# OperantFEDv6.net
KiCad netlist of a schematic drawn in EAGLE
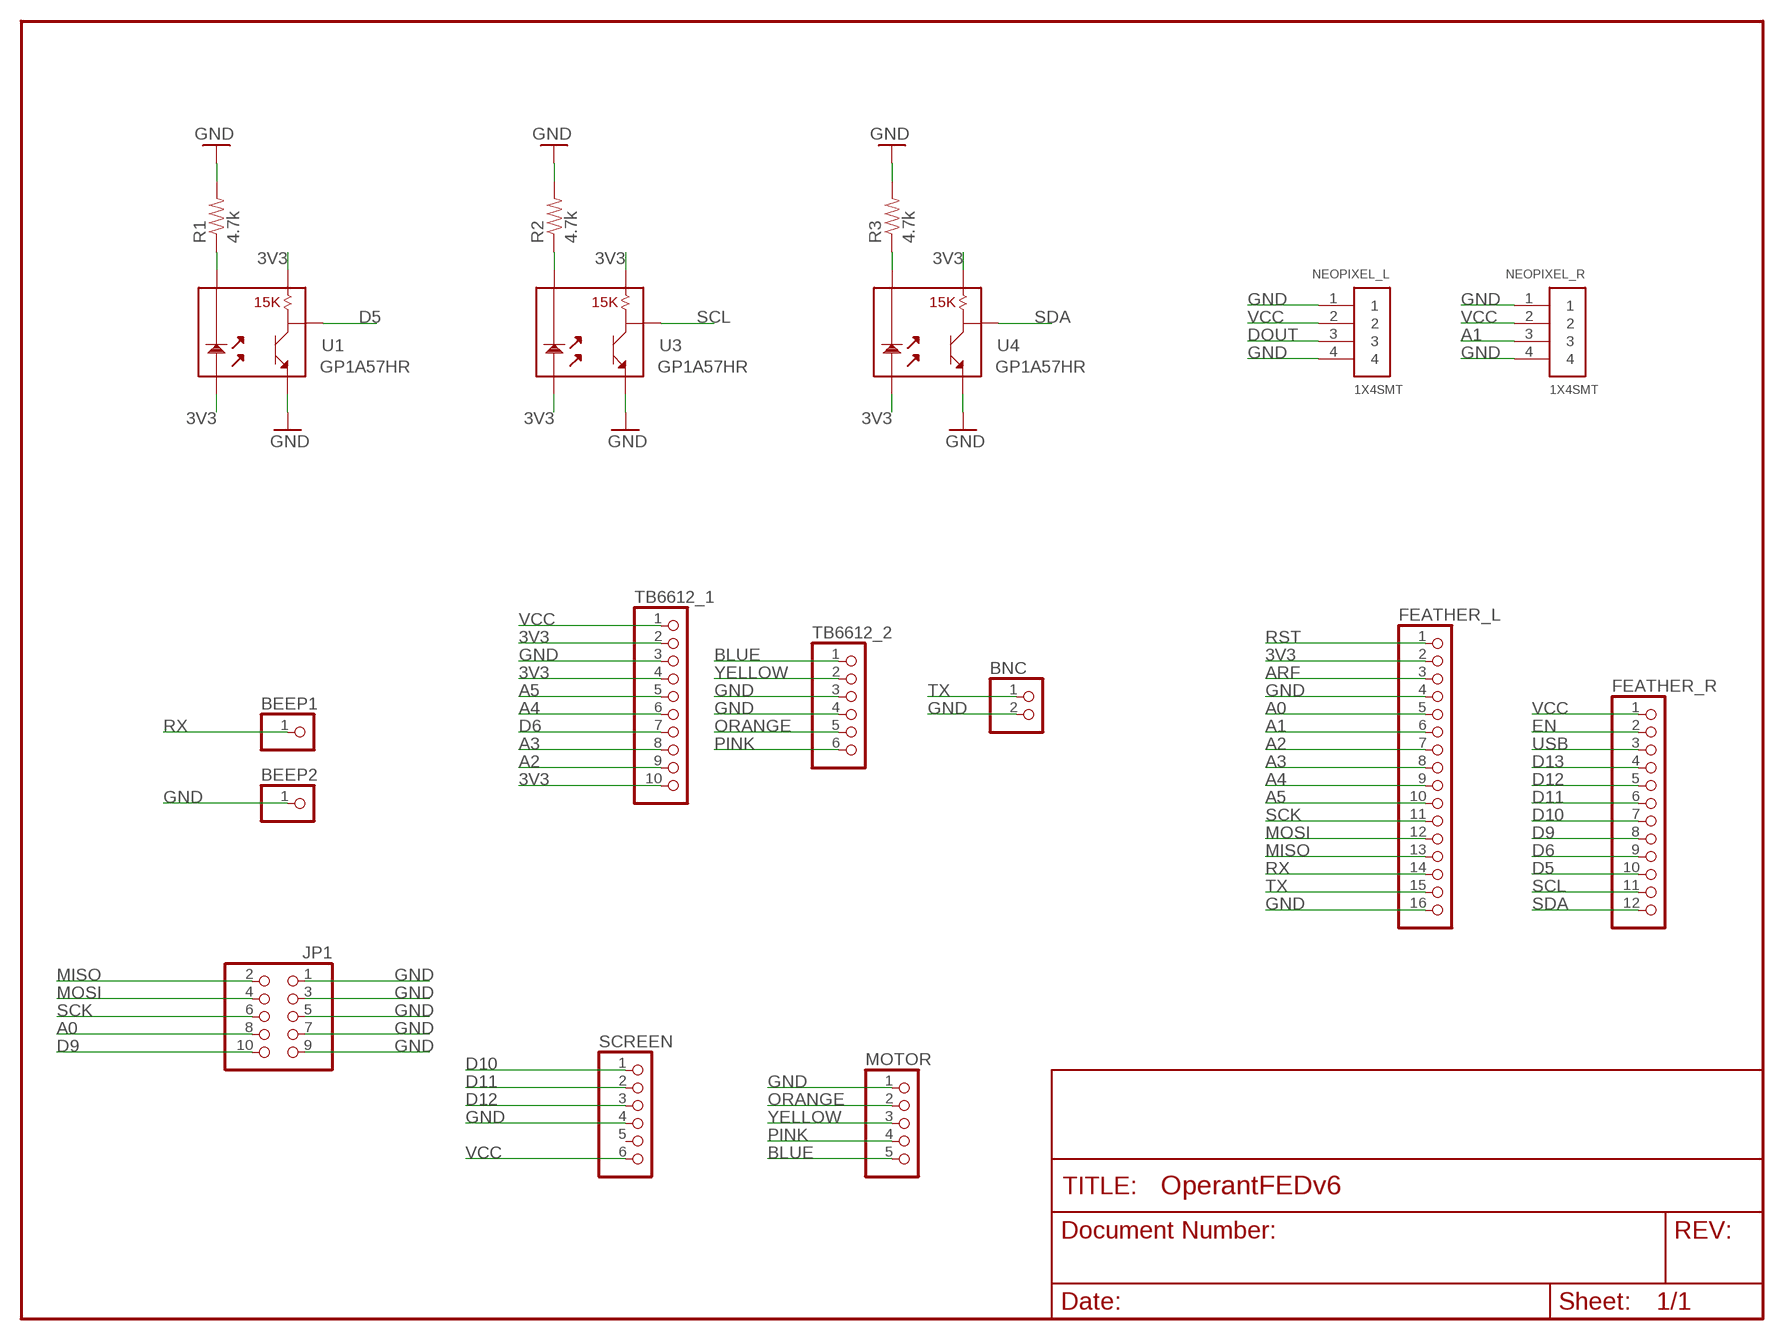
[diagram p0: schematic, sheet 1]

(export (version "E")
  (design (tool "Eeschema 10.0.6"))
  (components
    (comp (ref "BEEP1")
      (value "PINHD-1X1")
      (footprint "eagle-import:1X01")
      (libsource (lib "eagle-import") (part "PINHD-1X1"))
    )
    (comp (ref "BEEP2")
      (value "PINHD-1X1")
      (footprint "eagle-import:1X01")
      (libsource (lib "eagle-import") (part "PINHD-1X1"))
    )
    (comp (ref "BNC")
      (value "PINHD-1X2")
      (footprint "eagle-import:1X02")
      (libsource (lib "eagle-import") (part "PINHD-1X2"))
    )
    (comp (ref "FEATHER_L")
      (value "PINHD-1X16")
      (footprint "eagle-import:1X16")
      (libsource (lib "eagle-import") (part "PINHD-1X16"))
    )
    (comp (ref "FEATHER_R")
      (value "PINHD-1X12")
      (footprint "eagle-import:1X12")
      (libsource (lib "eagle-import") (part "PINHD-1X12"))
    )
    (comp (ref "JP1")
      (value "PINHD-2X5/90")
      (footprint "eagle-import:2X05_90")
      (libsource (lib "eagle-import") (part "PINHD-2X5/90"))
    )
    (comp (ref "MOTOR")
      (value "PINHD-1X5")
      (footprint "eagle-import:1X05")
      (libsource (lib "eagle-import") (part "PINHD-1X5"))
    )
    (comp (ref "NEOPIXEL_L")
      (value "1X4SMT")
      (footprint "eagle-import:1X4-SMT")
      (libsource (lib "eagle-import") (part "1X4SMT"))
    )
    (comp (ref "NEOPIXEL_R")
      (value "1X4SMT")
      (footprint "eagle-import:1X4-SMT")
      (libsource (lib "eagle-import") (part "1X4SMT"))
    )
    (comp (ref "R1")
      (value "4.7k")
      (footprint "eagle-import:AXIAL-0.3")
      (libsource (lib "eagle-import") (part "RESISTORPTH1"))
    )
    (comp (ref "R2")
      (value "4.7k")
      (footprint "eagle-import:AXIAL-0.3")
      (libsource (lib "eagle-import") (part "RESISTORPTH1"))
    )
    (comp (ref "R3")
      (value "4.7k")
      (footprint "eagle-import:AXIAL-0.3")
      (libsource (lib "eagle-import") (part "RESISTORPTH1"))
    )
    (comp (ref "SCREEN")
      (value "PINHD-1X6")
      (footprint "eagle-import:1X06")
      (libsource (lib "eagle-import") (part "PINHD-1X6"))
    )
    (comp (ref "TB6612_1")
      (value "PINHD-1X10")
      (footprint "eagle-import:1X10")
      (libsource (lib "eagle-import") (part "PINHD-1X10"))
    )
    (comp (ref "TB6612_2")
      (value "PINHD-1X6")
      (footprint "eagle-import:1X06")
      (libsource (lib "eagle-import") (part "PINHD-1X6"))
    )
    (comp (ref "U1")
      (value "GP1A57HR")
      (footprint "eagle-import:GP1A57HR")
      (libsource (lib "eagle-import") (part "GP1A57HR"))
    )
    (comp (ref "U3")
      (value "GP1A57HR")
      (footprint "eagle-import:GP1A57HR")
      (libsource (lib "eagle-import") (part "GP1A57HR"))
    )
    (comp (ref "U4")
      (value "GP1A57HR")
      (footprint "eagle-import:GP1A57HR")
      (libsource (lib "eagle-import") (part "GP1A57HR"))
    )
  )
  (nets
    (net (code "1") (name "/3V3") (class "Default")
      (node (ref "FEATHER_L") (pin "2") (pinfunction "2_2") (pintype "passive"))
      (node (ref "TB6612_1") (pin "10") (pinfunction "10_10") (pintype "passive"))
      (node (ref "TB6612_1") (pin "2") (pinfunction "2_2") (pintype "passive"))
      (node (ref "TB6612_1") (pin "4") (pinfunction "4_4") (pintype "passive"))
      (node (ref "U1") (pin "1") (pinfunction "1_1") (pintype "bidirectional"))
      (node (ref "U1") (pin "3") (pinfunction "3_3") (pintype "bidirectional"))
      (node (ref "U3") (pin "1") (pinfunction "1_1") (pintype "bidirectional"))
      (node (ref "U3") (pin "3") (pinfunction "3_3") (pintype "bidirectional"))
      (node (ref "U4") (pin "1") (pinfunction "1_1") (pintype "bidirectional"))
      (node (ref "U4") (pin "3") (pinfunction "3_3") (pintype "bidirectional"))
    )
    (net (code "2") (name "/A0") (class "Default")
      (node (ref "FEATHER_L") (pin "5") (pinfunction "5_5") (pintype "passive"))
      (node (ref "JP1") (pin "8") (pinfunction "8_8") (pintype "passive"))
    )
    (net (code "3") (name "/A1") (class "Default")
      (node (ref "FEATHER_L") (pin "6") (pinfunction "6_6") (pintype "passive"))
      (node (ref "NEOPIXEL_R") (pin "3") (pinfunction "3_3") (pintype "bidirectional"))
    )
    (net (code "4") (name "/A2") (class "Default")
      (node (ref "FEATHER_L") (pin "7") (pinfunction "7_7") (pintype "passive"))
      (node (ref "TB6612_1") (pin "9") (pinfunction "9_9") (pintype "passive"))
    )
    (net (code "5") (name "/A3") (class "Default")
      (node (ref "FEATHER_L") (pin "8") (pinfunction "8_8") (pintype "passive"))
      (node (ref "TB6612_1") (pin "8") (pinfunction "8_8") (pintype "passive"))
    )
    (net (code "6") (name "/A4") (class "Default")
      (node (ref "FEATHER_L") (pin "9") (pinfunction "9_9") (pintype "passive"))
      (node (ref "TB6612_1") (pin "6") (pinfunction "6_6") (pintype "passive"))
    )
    (net (code "7") (name "/A5") (class "Default")
      (node (ref "FEATHER_L") (pin "10") (pinfunction "10_10") (pintype "passive"))
      (node (ref "TB6612_1") (pin "5") (pinfunction "5_5") (pintype "passive"))
    )
    (net (code "8") (name "/ARF") (class "Default")
      (node (ref "FEATHER_L") (pin "3") (pinfunction "3_3") (pintype "passive"))
    )
    (net (code "9") (name "/BLUE") (class "Default")
      (node (ref "MOTOR") (pin "5") (pinfunction "5_5") (pintype "passive"))
      (node (ref "TB6612_2") (pin "1") (pinfunction "1_1") (pintype "passive"))
    )
    (net (code "10") (name "/D5") (class "Default")
      (node (ref "FEATHER_R") (pin "10") (pinfunction "10_10") (pintype "passive"))
      (node (ref "U1") (pin "4") (pinfunction "4_4") (pintype "bidirectional"))
    )
    (net (code "11") (name "/D6") (class "Default")
      (node (ref "FEATHER_R") (pin "9") (pinfunction "9_9") (pintype "passive"))
      (node (ref "TB6612_1") (pin "7") (pinfunction "7_7") (pintype "passive"))
    )
    (net (code "12") (name "/D9") (class "Default")
      (node (ref "FEATHER_R") (pin "8") (pinfunction "8_8") (pintype "passive"))
      (node (ref "JP1") (pin "10") (pinfunction "10_10") (pintype "passive"))
    )
    (net (code "13") (name "/D10") (class "Default")
      (node (ref "FEATHER_R") (pin "7") (pinfunction "7_7") (pintype "passive"))
      (node (ref "SCREEN") (pin "1") (pinfunction "1_1") (pintype "passive"))
    )
    (net (code "14") (name "/D11") (class "Default")
      (node (ref "FEATHER_R") (pin "6") (pinfunction "6_6") (pintype "passive"))
      (node (ref "SCREEN") (pin "2") (pinfunction "2_2") (pintype "passive"))
    )
    (net (code "15") (name "/D12") (class "Default")
      (node (ref "FEATHER_R") (pin "5") (pinfunction "5_5") (pintype "passive"))
      (node (ref "SCREEN") (pin "3") (pinfunction "3_3") (pintype "passive"))
    )
    (net (code "16") (name "/D13") (class "Default")
      (node (ref "FEATHER_R") (pin "4") (pinfunction "4_4") (pintype "passive"))
    )
    (net (code "17") (name "/DOUT") (class "Default")
      (node (ref "NEOPIXEL_L") (pin "3") (pinfunction "3_3") (pintype "bidirectional"))
    )
    (net (code "18") (name "/EN") (class "Default")
      (node (ref "FEATHER_R") (pin "2") (pinfunction "2_2") (pintype "passive"))
    )
    (net (code "19") (name "/MISO") (class "Default")
      (node (ref "FEATHER_L") (pin "13") (pinfunction "13_13") (pintype "passive"))
      (node (ref "JP1") (pin "2") (pinfunction "2_2") (pintype "passive"))
    )
    (net (code "20") (name "/MOSI") (class "Default")
      (node (ref "FEATHER_L") (pin "12") (pinfunction "12_12") (pintype "passive"))
      (node (ref "JP1") (pin "4") (pinfunction "4_4") (pintype "passive"))
    )
    (net (code "21") (name "/ORANGE") (class "Default")
      (node (ref "MOTOR") (pin "2") (pinfunction "2_2") (pintype "passive"))
      (node (ref "TB6612_2") (pin "5") (pinfunction "5_5") (pintype "passive"))
    )
    (net (code "22") (name "/PINK") (class "Default")
      (node (ref "MOTOR") (pin "4") (pinfunction "4_4") (pintype "passive"))
      (node (ref "TB6612_2") (pin "6") (pinfunction "6_6") (pintype "passive"))
    )
    (net (code "23") (name "/RST") (class "Default")
      (node (ref "FEATHER_L") (pin "1") (pinfunction "1_1") (pintype "passive"))
    )
    (net (code "24") (name "/RX") (class "Default")
      (node (ref "BEEP1") (pin "1") (pinfunction "1_1") (pintype "passive"))
      (node (ref "FEATHER_L") (pin "14") (pinfunction "14_14") (pintype "passive"))
    )
    (net (code "25") (name "/SCK") (class "Default")
      (node (ref "FEATHER_L") (pin "11") (pinfunction "11_11") (pintype "passive"))
      (node (ref "JP1") (pin "6") (pinfunction "6_6") (pintype "passive"))
    )
    (net (code "26") (name "/SCL") (class "Default")
      (node (ref "FEATHER_R") (pin "11") (pinfunction "11_11") (pintype "passive"))
      (node (ref "U3") (pin "4") (pinfunction "4_4") (pintype "bidirectional"))
    )
    (net (code "27") (name "/SDA") (class "Default")
      (node (ref "FEATHER_R") (pin "12") (pinfunction "12_12") (pintype "passive"))
      (node (ref "U4") (pin "4") (pinfunction "4_4") (pintype "bidirectional"))
    )
    (net (code "28") (name "/TX") (class "Default")
      (node (ref "BNC") (pin "1") (pinfunction "1_1") (pintype "passive"))
      (node (ref "FEATHER_L") (pin "15") (pinfunction "15_15") (pintype "passive"))
    )
    (net (code "29") (name "/USB") (class "Default")
      (node (ref "FEATHER_R") (pin "3") (pinfunction "3_3") (pintype "passive"))
    )
    (net (code "30") (name "/VCC") (class "Default")
      (node (ref "FEATHER_R") (pin "1") (pinfunction "1_1") (pintype "passive"))
      (node (ref "NEOPIXEL_L") (pin "2") (pinfunction "2_2") (pintype "bidirectional"))
      (node (ref "NEOPIXEL_R") (pin "2") (pinfunction "2_2") (pintype "bidirectional"))
      (node (ref "SCREEN") (pin "6") (pinfunction "6_6") (pintype "passive"))
      (node (ref "TB6612_1") (pin "1") (pinfunction "1_1") (pintype "passive"))
    )
    (net (code "31") (name "/YELLOW") (class "Default")
      (node (ref "MOTOR") (pin "3") (pinfunction "3_3") (pintype "passive"))
      (node (ref "TB6612_2") (pin "2") (pinfunction "2_2") (pintype "passive"))
    )
    (net (code "32") (name "GND") (class "Default")
      (node (ref "BEEP2") (pin "1") (pinfunction "1_1") (pintype "passive"))
      (node (ref "BNC") (pin "2") (pinfunction "2_2") (pintype "passive"))
      (node (ref "FEATHER_L") (pin "16") (pinfunction "16_16") (pintype "passive"))
      (node (ref "FEATHER_L") (pin "4") (pinfunction "4_4") (pintype "passive"))
      (node (ref "JP1") (pin "1") (pinfunction "1_1") (pintype "passive"))
      (node (ref "JP1") (pin "3") (pinfunction "3_3") (pintype "passive"))
      (node (ref "JP1") (pin "5") (pinfunction "5_5") (pintype "passive"))
      (node (ref "JP1") (pin "7") (pinfunction "7_7") (pintype "passive"))
      (node (ref "JP1") (pin "9") (pinfunction "9_9") (pintype "passive"))
      (node (ref "MOTOR") (pin "1") (pinfunction "1_1") (pintype "passive"))
      (node (ref "NEOPIXEL_L") (pin "1") (pinfunction "1_1") (pintype "bidirectional"))
      (node (ref "NEOPIXEL_L") (pin "4") (pinfunction "4_4") (pintype "bidirectional"))
      (node (ref "NEOPIXEL_R") (pin "1") (pinfunction "1_1") (pintype "bidirectional"))
      (node (ref "NEOPIXEL_R") (pin "4") (pinfunction "4_4") (pintype "bidirectional"))
      (node (ref "R1") (pin "P$2") (pinfunction "2_P$2") (pintype "passive"))
      (node (ref "R2") (pin "P$2") (pinfunction "2_P$2") (pintype "passive"))
      (node (ref "R3") (pin "P$2") (pinfunction "2_P$2") (pintype "passive"))
      (node (ref "SCREEN") (pin "4") (pinfunction "4_4") (pintype "passive"))
      (node (ref "TB6612_1") (pin "3") (pinfunction "3_3") (pintype "passive"))
      (node (ref "TB6612_2") (pin "3") (pinfunction "3_3") (pintype "passive"))
      (node (ref "TB6612_2") (pin "4") (pinfunction "4_4") (pintype "passive"))
      (node (ref "U1") (pin "5") (pinfunction "5_5") (pintype "bidirectional"))
      (node (ref "U3") (pin "5") (pinfunction "5_5") (pintype "bidirectional"))
      (node (ref "U4") (pin "5") (pinfunction "5_5") (pintype "bidirectional"))
    )
    (net (code "33") (name "Net-(R1-1)") (class "Default")
      (node (ref "R1") (pin "P$1") (pinfunction "1_P$1") (pintype "passive"))
      (node (ref "U1") (pin "2") (pinfunction "2_2") (pintype "bidirectional"))
    )
    (net (code "34") (name "Net-(R2-1)") (class "Default")
      (node (ref "R2") (pin "P$1") (pinfunction "1_P$1") (pintype "passive"))
      (node (ref "U3") (pin "2") (pinfunction "2_2") (pintype "bidirectional"))
    )
    (net (code "35") (name "Net-(R3-1)") (class "Default")
      (node (ref "R3") (pin "P$1") (pinfunction "1_P$1") (pintype "passive"))
      (node (ref "U4") (pin "2") (pinfunction "2_2") (pintype "bidirectional"))
    )
    (net (code "36") (name "unconnected-(SCREEN-Pad5)") (class "Default")
      (node (ref "SCREEN") (pin "5") (pinfunction "5_5") (pintype "passive"))
    )
  )
)
